# Boost_Gauge_MainBoard.net
KiCad netlist of a schematic drawn in EAGLE
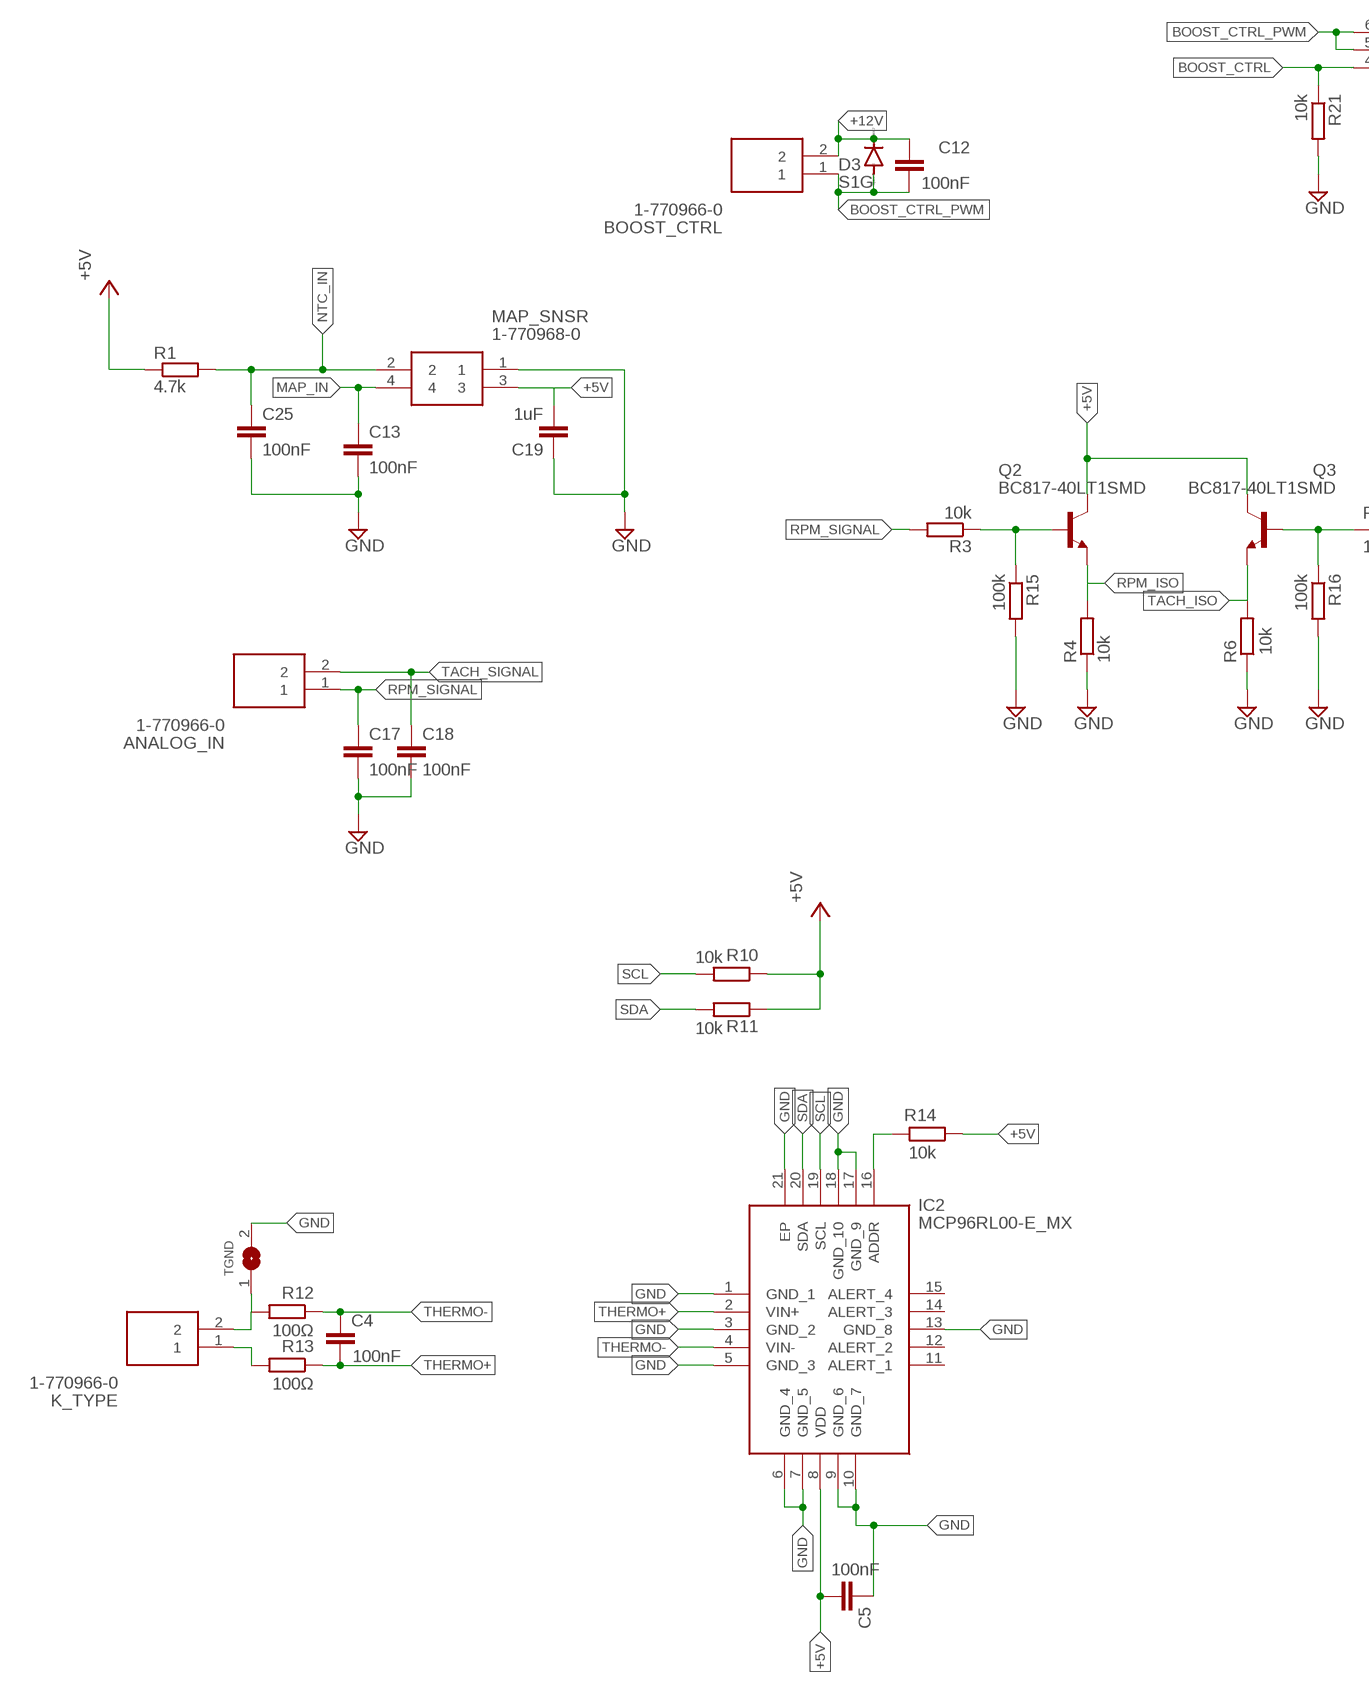
[diagram p0: schematic, sheet 1, part 1 of 2]
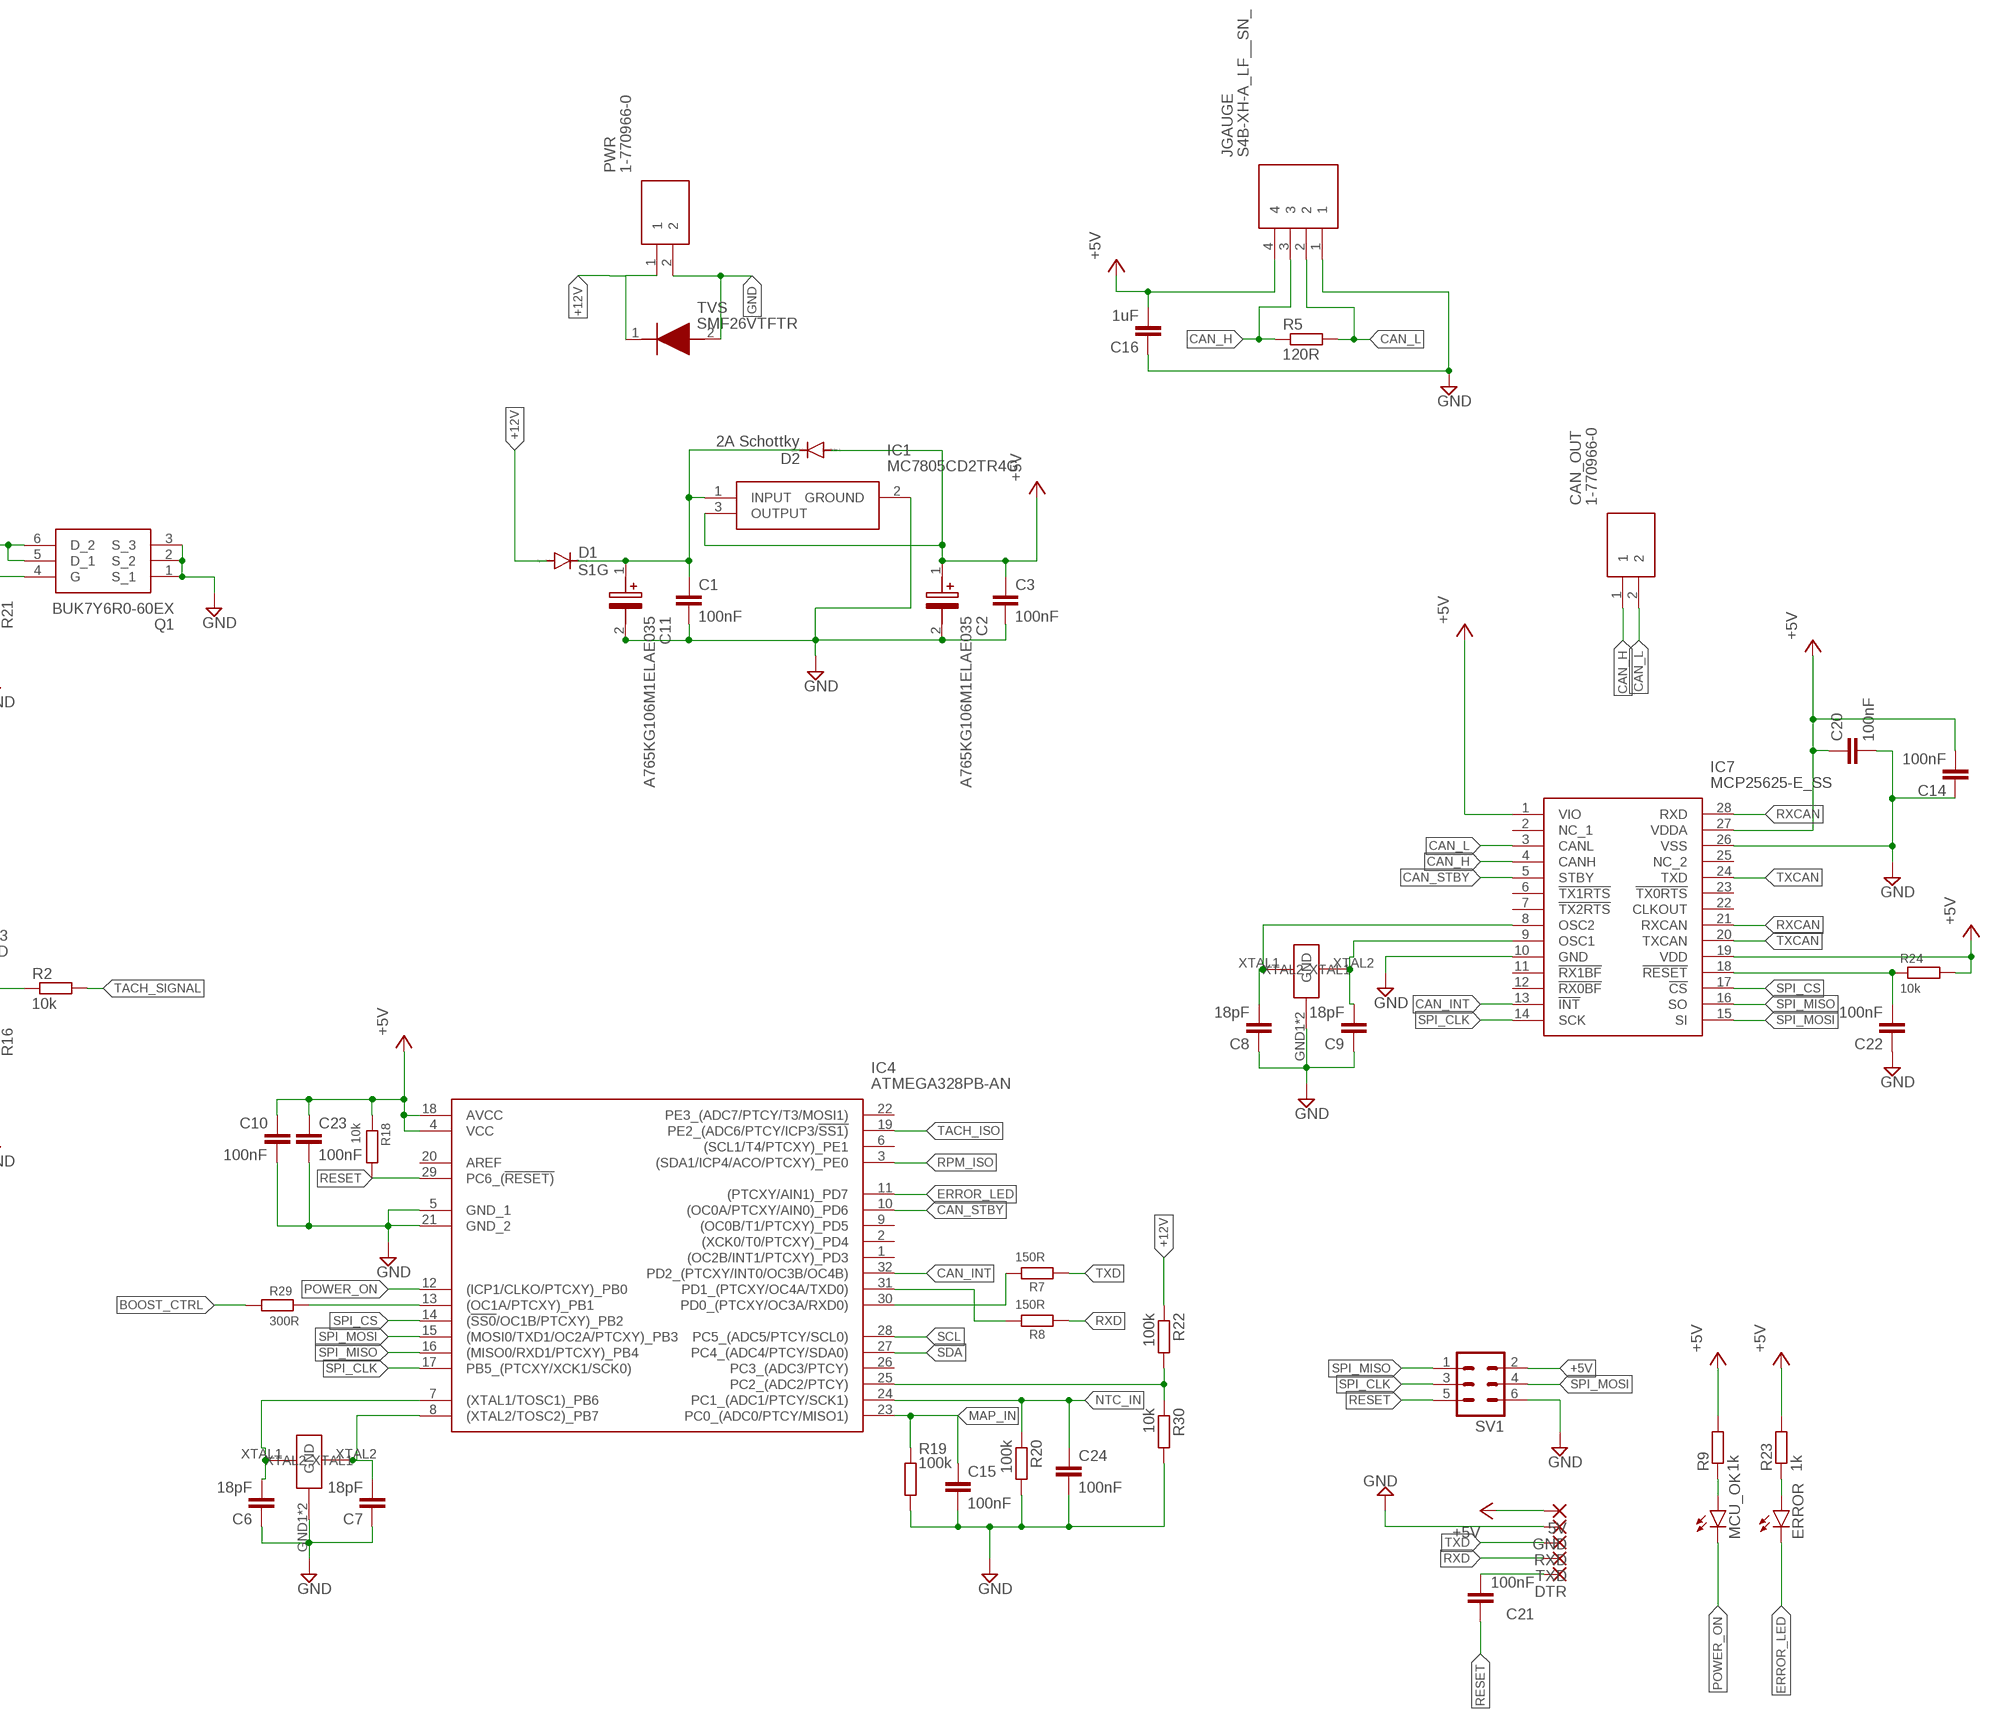
[diagram p1: schematic, sheet 1, part 2 of 2]

(export (version "E")
  (design (tool "Eeschema 10.0.6"))
  (components
    (comp (ref "5V")
      (value "1,6/0,9")
      (footprint "eagle-import:1,6_0,9")
      (libsource (lib "eagle-import") (part "1,6/0,9"))
    )
    (comp (ref "ANALOG_IN")
      (value "1-770966-0")
      (footprint "eagle-import:17709660")
      (fields (field (name "MOUSER_PART_NUMBER") "571-1-770966-0"))
      (libsource (lib "eagle-import") (part "1-770966-0"))
    )
    (comp (ref "BOOST_CTRL")
      (value "1-770966-0")
      (footprint "eagle-import:17709660")
      (fields (field (name "MOUSER_PART_NUMBER") "571-1-770966-0"))
      (libsource (lib "eagle-import") (part "1-770966-0"))
    )
    (comp (ref "C1")
      (value "100nF")
      (footprint "eagle-import:C0805")
      (libsource (lib "eagle-import") (part "C-EUC0805"))
    )
    (comp (ref "C2")
      (value "A765KG106M1ELAE035")
      (footprint "eagle-import:CAPAE830X730N")
      (fields (field (name "MOUSER_PART_NUMBER") "80-A765KG106M1ELAE35"))
      (libsource (lib "eagle-import") (part "A765KG106M1ELAE035"))
    )
    (comp (ref "C3")
      (value "100nF")
      (footprint "eagle-import:C0805")
      (libsource (lib "eagle-import") (part "C-EUC0805"))
    )
    (comp (ref "C4")
      (value "100nF")
      (footprint "eagle-import:C0805")
      (libsource (lib "eagle-import") (part "C-EUC0805"))
    )
    (comp (ref "C5")
      (value "100nF")
      (footprint "eagle-import:C0805")
      (libsource (lib "eagle-import") (part "C-EUC0805"))
    )
    (comp (ref "C6")
      (value "18pF")
      (footprint "eagle-import:C0805")
      (libsource (lib "eagle-import") (part "C-EUC0805"))
    )
    (comp (ref "C7")
      (value "18pF")
      (footprint "eagle-import:C0805")
      (libsource (lib "eagle-import") (part "C-EUC0805"))
    )
    (comp (ref "C8")
      (value "18pF")
      (footprint "eagle-import:C0805")
      (libsource (lib "eagle-import") (part "C-EUC0805"))
    )
    (comp (ref "C9")
      (value "18pF")
      (footprint "eagle-import:C0805")
      (libsource (lib "eagle-import") (part "C-EUC0805"))
    )
    (comp (ref "C10")
      (value "100nF")
      (footprint "eagle-import:C0805")
      (libsource (lib "eagle-import") (part "C-EUC0805"))
    )
    (comp (ref "C11")
      (value "A765KG106M1ELAE035")
      (footprint "eagle-import:CAPAE830X730N")
      (fields (field (name "MOUSER_PART_NUMBER") "80-A765KG106M1ELAE35"))
      (libsource (lib "eagle-import") (part "A765KG106M1ELAE035"))
    )
    (comp (ref "C12")
      (value "100nF")
      (footprint "eagle-import:C0805")
      (libsource (lib "eagle-import") (part "C-EUC0805"))
    )
    (comp (ref "C13")
      (value "100nF")
      (footprint "eagle-import:C0805")
      (libsource (lib "eagle-import") (part "C-EUC0805"))
    )
    (comp (ref "C14")
      (value "100nF")
      (footprint "eagle-import:C0805")
      (libsource (lib "eagle-import") (part "C-EUC0805"))
    )
    (comp (ref "C15")
      (value "100nF")
      (footprint "eagle-import:C0805")
      (libsource (lib "eagle-import") (part "C-EUC0805"))
    )
    (comp (ref "C16")
      (value "1uF")
      (footprint "eagle-import:C0805")
      (libsource (lib "eagle-import") (part "C-EUC0805"))
    )
    (comp (ref "C17")
      (value "100nF")
      (footprint "eagle-import:C0805")
      (libsource (lib "eagle-import") (part "C-EUC0805"))
    )
    (comp (ref "C18")
      (value "100nF")
      (footprint "eagle-import:C0805")
      (libsource (lib "eagle-import") (part "C-EUC0805"))
    )
    (comp (ref "C19")
      (value "1uF")
      (footprint "eagle-import:C0805")
      (libsource (lib "eagle-import") (part "C-EUC0805"))
    )
    (comp (ref "C20")
      (value "100nF")
      (footprint "eagle-import:C0805")
      (libsource (lib "eagle-import") (part "C-EUC0805"))
    )
    (comp (ref "C21")
      (value "100nF")
      (footprint "eagle-import:C0805")
      (libsource (lib "eagle-import") (part "C-EUC0805"))
    )
    (comp (ref "C22")
      (value "100nF")
      (footprint "eagle-import:C0805")
      (libsource (lib "eagle-import") (part "C-EUC0805"))
    )
    (comp (ref "C23")
      (value "100nF")
      (footprint "eagle-import:C0805")
      (libsource (lib "eagle-import") (part "C-EUC0805"))
    )
    (comp (ref "C24")
      (value "100nF")
      (footprint "eagle-import:C0805")
      (libsource (lib "eagle-import") (part "C-EUC0805"))
    )
    (comp (ref "C25")
      (value "100nF")
      (footprint "eagle-import:C0805")
      (libsource (lib "eagle-import") (part "C-EUC0805"))
    )
    (comp (ref "CAN_OUT")
      (value "1-770966-0")
      (footprint "eagle-import:17709660")
      (fields (field (name "MOUSER_PART_NUMBER") "571-1-770966-0"))
      (libsource (lib "eagle-import") (part "1-770966-0"))
    )
    (comp (ref "D1")
      (value "S1G")
      (footprint "eagle-import:DO-214AC")
      (libsource (lib "eagle-import") (part "DIODE-DO-214AC"))
    )
    (comp (ref "D2")
      (value "2A Schottky")
      (footprint "eagle-import:DO-214AC")
      (libsource (lib "eagle-import") (part "DIODE-DO-214AC"))
    )
    (comp (ref "D3")
      (value "S1G")
      (footprint "eagle-import:DO-214AC")
      (libsource (lib "eagle-import") (part "DIODE-DO-214AC"))
    )
    (comp (ref "DTR")
      (value "1,6/0,9")
      (footprint "eagle-import:1,6_0,9")
      (libsource (lib "eagle-import") (part "1,6/0,9"))
    )
    (comp (ref "ERROR")
      (value "LEDCHIPLED_1206")
      (footprint "eagle-import:CHIPLED_1206")
      (libsource (lib "eagle-import") (part "LEDCHIPLED_1206"))
    )
    (comp (ref "GND")
      (value "1,6/0,9")
      (footprint "eagle-import:1,6_0,9")
      (libsource (lib "eagle-import") (part "1,6/0,9"))
    )
    (comp (ref "IC1")
      (value "MC7805CD2TR4G")
      (footprint "eagle-import:MC7805CD2TR4G")
      (fields (field (name "MOUSER_PART_NUMBER") "863-MC7805CD2TR4G"))
      (libsource (lib "eagle-import") (part "MC7805CD2TR4G"))
    )
    (comp (ref "IC2")
      (value "MCP96RL00-E_MX")
      (footprint "eagle-import:QFN65P500X500X100-21N")
      (fields
        (field (name "MANUFACTURER_PART_NUMBER") "MCP96RL00-E/MX")
        (field (name "MOUSER_PART_NUMBER") "579-MCP96RL00-E/MX")
      )
      (libsource (lib "eagle-import") (part "MCP96RL00-E_MX"))
    )
    (comp (ref "IC4")
      (value "ATMEGA328PB-AN")
      (footprint "eagle-import:QFP80P900X900X120-32N")
      (fields (field (name "MOUSER_PART_NUMBER") "556-ATMEGA328PB-AN"))
      (libsource (lib "eagle-import") (part "ATMEGA328PB-AN"))
    )
    (comp (ref "IC7")
      (value "MCP25625-E_SS")
      (footprint "eagle-import:SOP65P780X200-28N")
      (fields
        (field (name "MANUFACTURER_PART_NUMBER") "MCP25625-E/SS")
        (field (name "MOUSER_PART_NUMBER") "579-MCP25625-E/SS")
      )
      (libsource (lib "eagle-import") (part "MCP25625-E_SS"))
    )
    (comp (ref "JGAUGE")
      (value "S4B-XH-A_LF__SN_")
      (footprint "eagle-import:S4BXHALFSN")
      (fields (field (name "MANUFACTURER_PART_NUMBER") "S4B-XH-A(LF)(SN)"))
      (libsource (lib "eagle-import") (part "S4B-XH-A_LF__SN_"))
    )
    (comp (ref "K_TYPE")
      (value "1-770966-0")
      (footprint "eagle-import:17709660")
      (fields (field (name "MOUSER_PART_NUMBER") "571-1-770966-0"))
      (libsource (lib "eagle-import") (part "1-770966-0"))
    )
    (comp (ref "MAP_SNSR")
      (value "1-770968-0")
      (footprint "eagle-import:17709680")
      (fields (field (name "MOUSER_PART_NUMBER") "571-1-770968-0"))
      (libsource (lib "eagle-import") (part "1-770968-0"))
    )
    (comp (ref "MCU_OK")
      (value "LEDCHIPLED_1206")
      (footprint "eagle-import:CHIPLED_1206")
      (libsource (lib "eagle-import") (part "LEDCHIPLED_1206"))
    )
    (comp (ref "PWR")
      (value "1-770966-0")
      (footprint "eagle-import:17709660")
      (fields (field (name "MOUSER_PART_NUMBER") "571-1-770966-0"))
      (libsource (lib "eagle-import") (part "1-770966-0"))
    )
    (comp (ref "Q1")
      (value "BUK7Y6R0-60EX")
      (footprint "eagle-import:BUK7Y6R060EX")
      (fields (field (name "MOUSER_PART_NUMBER") "771-BUK7Y6R0-60EX"))
      (libsource (lib "eagle-import") (part "BUK7Y6R0-60EX"))
    )
    (comp (ref "Q2")
      (value "BC817-40LT1SMD")
      (footprint "eagle-import:SOT23-BEC")
      (libsource (lib "eagle-import") (part "BC817SMD-40LT1"))
    )
    (comp (ref "Q3")
      (value "BC817-40LT1SMD")
      (footprint "eagle-import:SOT23-BEC")
      (libsource (lib "eagle-import") (part "BC817SMD-40LT1"))
    )
    (comp (ref "R1")
      (value "4.7k")
      (footprint "eagle-import:R0805")
      (libsource (lib "eagle-import") (part "R-EU_R0805"))
    )
    (comp (ref "R2")
      (value "10k")
      (footprint "eagle-import:R0805")
      (libsource (lib "eagle-import") (part "R-EU_R0805"))
    )
    (comp (ref "R3")
      (value "10k")
      (footprint "eagle-import:R0805")
      (libsource (lib "eagle-import") (part "R-EU_R0805"))
    )
    (comp (ref "R4")
      (value "10k")
      (footprint "eagle-import:R0805")
      (libsource (lib "eagle-import") (part "R-EU_R0805"))
    )
    (comp (ref "R5")
      (value "120R")
      (footprint "eagle-import:R1206")
      (libsource (lib "eagle-import") (part "R-EU_R1206"))
    )
    (comp (ref "R6")
      (value "10k")
      (footprint "eagle-import:R0805")
      (libsource (lib "eagle-import") (part "R-EU_R0805"))
    )
    (comp (ref "R7")
      (value "150R")
      (footprint "eagle-import:R0805")
      (libsource (lib "eagle-import") (part "R-EU_R0805"))
    )
    (comp (ref "R8")
      (value "150R")
      (footprint "eagle-import:R0805")
      (libsource (lib "eagle-import") (part "R-EU_R0805"))
    )
    (comp (ref "R9")
      (value "1k")
      (footprint "eagle-import:R0805")
      (libsource (lib "eagle-import") (part "R-EU_R0805"))
    )
    (comp (ref "R10")
      (value "10k")
      (footprint "eagle-import:R0805")
      (libsource (lib "eagle-import") (part "R-EU_R0805"))
    )
    (comp (ref "R11")
      (value "10k")
      (footprint "eagle-import:R0805")
      (libsource (lib "eagle-import") (part "R-EU_R0805"))
    )
    (comp (ref "R12")
      (value "100Ω")
      (footprint "eagle-import:R0805")
      (libsource (lib "eagle-import") (part "R-EU_R0805"))
    )
    (comp (ref "R13")
      (value "100Ω")
      (footprint "eagle-import:R0805")
      (libsource (lib "eagle-import") (part "R-EU_R0805"))
    )
    (comp (ref "R14")
      (value "10k")
      (footprint "eagle-import:R0805")
      (libsource (lib "eagle-import") (part "R-EU_R0805"))
    )
    (comp (ref "R15")
      (value "100k")
      (footprint "eagle-import:R0805")
      (libsource (lib "eagle-import") (part "R-EU_R0805"))
    )
    (comp (ref "R16")
      (value "100k")
      (footprint "eagle-import:R0805")
      (libsource (lib "eagle-import") (part "R-EU_R0805"))
    )
    (comp (ref "R18")
      (value "10k")
      (footprint "eagle-import:R0805")
      (libsource (lib "eagle-import") (part "R-EU_R0805"))
    )
    (comp (ref "R19")
      (value "100k")
      (footprint "eagle-import:R0805")
      (libsource (lib "eagle-import") (part "R-EU_R0805"))
    )
    (comp (ref "R20")
      (value "100k")
      (footprint "eagle-import:R0805")
      (libsource (lib "eagle-import") (part "R-EU_R0805"))
    )
    (comp (ref "R21")
      (value "10k")
      (footprint "eagle-import:R0805")
      (libsource (lib "eagle-import") (part "R-EU_R0805"))
    )
    (comp (ref "R22")
      (value "100k")
      (footprint "eagle-import:R0805")
      (libsource (lib "eagle-import") (part "R-EU_R0805"))
    )
    (comp (ref "R23")
      (value "1k")
      (footprint "eagle-import:R0805")
      (libsource (lib "eagle-import") (part "R-EU_R0805"))
    )
    (comp (ref "R24")
      (value "10k")
      (footprint "eagle-import:R0805")
      (libsource (lib "eagle-import") (part "R-EU_R0805"))
    )
    (comp (ref "R29")
      (value "300R")
      (footprint "eagle-import:R0805")
      (libsource (lib "eagle-import") (part "R-EU_R0805"))
    )
    (comp (ref "R30")
      (value "10k")
      (footprint "eagle-import:R0805")
      (libsource (lib "eagle-import") (part "R-EU_R0805"))
    )
    (comp (ref "RXD")
      (value "1,6/0,9")
      (footprint "eagle-import:1,6_0,9")
      (libsource (lib "eagle-import") (part "1,6/0,9"))
    )
    (comp (ref "SV1")
      (value "MA03-2")
      (footprint "eagle-import:MA03-2")
      (libsource (lib "eagle-import") (part "MA03-2"))
    )
    (comp (ref "TGND")
      (value "SOLDERJUMPER")
      (footprint "eagle-import:SOLDERJUMPER_ARROW_NOPASTE")
      (libsource (lib "eagle-import") (part "SOLDERJUMPER"))
    )
    (comp (ref "TVS")
      (value "SMF26VTFTR")
      (footprint "eagle-import:SMF26VTFTR")
      (fields (field (name "MOUSER_PART_NUMBER") "755-SMF26VTFTR"))
      (libsource (lib "eagle-import") (part "SMF26VTFTR"))
    )
    (comp (ref "TXD")
      (value "1,6/0,9")
      (footprint "eagle-import:1,6_0,9")
      (libsource (lib "eagle-import") (part "1,6/0,9"))
    )
    (comp (ref "U$4")
      (value "E3X160181X04")
      (footprint "eagle-import:E3X160181X04")
      (libsource (lib "eagle-import") (part "E3X160181X04"))
    )
    (comp (ref "U$5")
      (value "E3X160181X04")
      (footprint "eagle-import:E3X160181X04")
      (libsource (lib "eagle-import") (part "E3X160181X04"))
    )
  )
  (nets
    (net (code "1") (name "+5V") (class "Default")
      (node (ref "5V") (pin "1") (pinfunction "P_1") (pintype "passive"))
      (node (ref "C10") (pin "1") (pinfunction "1_1") (pintype "passive"))
      (node (ref "C14") (pin "2") (pinfunction "2_2") (pintype "passive"))
      (node (ref "C16") (pin "2") (pinfunction "2_2") (pintype "passive"))
      (node (ref "C19") (pin "2") (pinfunction "2_2") (pintype "passive"))
      (node (ref "C2") (pin "1") (pinfunction "+_1") (pintype "bidirectional"))
      (node (ref "C20") (pin "1") (pinfunction "1_1") (pintype "passive"))
      (node (ref "C23") (pin "1") (pinfunction "1_1") (pintype "passive"))
      (node (ref "C3") (pin "1") (pinfunction "1_1") (pintype "passive"))
      (node (ref "C5") (pin "2") (pinfunction "2_2") (pintype "passive"))
      (node (ref "D2") (pin "A") (pinfunction "A_A") (pintype "passive"))
      (node (ref "IC1") (pin "3") (pinfunction "OUTPUT_3") (pintype "bidirectional"))
      (node (ref "IC2") (pin "8") (pinfunction "VDD_8") (pintype "bidirectional"))
      (node (ref "IC4") (pin "18") (pinfunction "AVCC_18") (pintype "bidirectional"))
      (node (ref "IC4") (pin "4") (pinfunction "VCC_4") (pintype "bidirectional"))
      (node (ref "IC7") (pin "1") (pinfunction "VIO_1") (pintype "bidirectional"))
      (node (ref "IC7") (pin "19") (pinfunction "VDD_19") (pintype "bidirectional"))
      (node (ref "IC7") (pin "27") (pinfunction "VDDA_27") (pintype "bidirectional"))
      (node (ref "JGAUGE") (pin "4") (pinfunction "4_4") (pintype "bidirectional"))
      (node (ref "MAP_SNSR") (pin "3") (pinfunction "3_3") (pintype "bidirectional"))
      (node (ref "Q2") (pin "C") (pinfunction "C_C") (pintype "passive"))
      (node (ref "Q3") (pin "C") (pinfunction "C_C") (pintype "passive"))
      (node (ref "R1") (pin "1") (pinfunction "1_1") (pintype "passive"))
      (node (ref "R10") (pin "1") (pinfunction "1_1") (pintype "passive"))
      (node (ref "R11") (pin "1") (pinfunction "1_1") (pintype "passive"))
      (node (ref "R14") (pin "1") (pinfunction "1_1") (pintype "passive"))
      (node (ref "R18") (pin "1") (pinfunction "1_1") (pintype "passive"))
      (node (ref "R23") (pin "2") (pinfunction "2_2") (pintype "passive"))
      (node (ref "R24") (pin "2") (pinfunction "2_2") (pintype "passive"))
      (node (ref "R9") (pin "2") (pinfunction "2_2") (pintype "passive"))
      (node (ref "SV1") (pin "2") (pinfunction "2_2") (pintype "passive"))
    )
    (net (code "2") (name "+12V") (class "Default")
      (node (ref "BOOST_CTRL") (pin "2") (pinfunction "2_2") (pintype "bidirectional"))
      (node (ref "C12") (pin "2") (pinfunction "2_2") (pintype "passive"))
      (node (ref "D1") (pin "A") (pinfunction "A_A") (pintype "passive"))
      (node (ref "D3") (pin "C") (pinfunction "C_C") (pintype "passive"))
      (node (ref "PWR") (pin "1") (pinfunction "1_1") (pintype "bidirectional"))
      (node (ref "R22") (pin "1") (pinfunction "1_1") (pintype "passive"))
      (node (ref "TVS") (pin "1") (pinfunction "K_1") (pintype "bidirectional"))
    )
    (net (code "3") (name "BOOST_CTRL") (class "Default")
      (node (ref "Q1") (pin "4") (pinfunction "G_4") (pintype "bidirectional"))
      (node (ref "R21") (pin "1") (pinfunction "1_1") (pintype "passive"))
      (node (ref "R29") (pin "1") (pinfunction "1_1") (pintype "passive"))
    )
    (net (code "4") (name "BOOST_CTRL_PWM") (class "Default")
      (node (ref "BOOST_CTRL") (pin "1") (pinfunction "1_1") (pintype "bidirectional"))
      (node (ref "C12") (pin "1") (pinfunction "1_1") (pintype "passive"))
      (node (ref "D3") (pin "A") (pinfunction "A_A") (pintype "passive"))
      (node (ref "Q1") (pin "5") (pinfunction "D_1_5") (pintype "bidirectional"))
      (node (ref "Q1") (pin "6") (pinfunction "D_2_6") (pintype "bidirectional"))
    )
    (net (code "5") (name "CAN_H") (class "Default")
      (node (ref "CAN_OUT") (pin "1") (pinfunction "1_1") (pintype "bidirectional"))
      (node (ref "IC7") (pin "4") (pinfunction "CANH_4") (pintype "bidirectional"))
      (node (ref "JGAUGE") (pin "3") (pinfunction "3_3") (pintype "bidirectional"))
      (node (ref "R5") (pin "1") (pinfunction "1_1") (pintype "passive"))
    )
    (net (code "6") (name "CAN_INT") (class "Default")
      (node (ref "IC4") (pin "32") (pinfunction "PD2_(PTCXY/INT0/OC3B/OC4B)_32") (pintype "bidirectional"))
      (node (ref "IC7") (pin "13") (pinfunction "~{INT}_13") (pintype "bidirectional"))
    )
    (net (code "7") (name "CAN_L") (class "Default")
      (node (ref "CAN_OUT") (pin "2") (pinfunction "2_2") (pintype "bidirectional"))
      (node (ref "IC7") (pin "3") (pinfunction "CANL_3") (pintype "bidirectional"))
      (node (ref "JGAUGE") (pin "2") (pinfunction "2_2") (pintype "bidirectional"))
      (node (ref "R5") (pin "2") (pinfunction "2_2") (pintype "passive"))
    )
    (net (code "8") (name "CAN_STBY") (class "Default")
      (node (ref "IC4") (pin "10") (pinfunction "(OC0A/PTCXY/AIN0)_PD6_10") (pintype "bidirectional"))
      (node (ref "IC7") (pin "5") (pinfunction "STBY_5") (pintype "bidirectional"))
    )
    (net (code "9") (name "ERROR_LED") (class "Default")
      (node (ref "ERROR") (pin "C") (pinfunction "C_C") (pintype "passive"))
      (node (ref "IC4") (pin "11") (pinfunction "(PTCXY/AIN1)_PD7_11") (pintype "bidirectional"))
    )
    (net (code "10") (name "GND") (class "Default")
      (node (ref "C1") (pin "2") (pinfunction "2_2") (pintype "passive"))
      (node (ref "C10") (pin "2") (pinfunction "2_2") (pintype "passive"))
      (node (ref "C11") (pin "2") (pinfunction "-_2") (pintype "bidirectional"))
      (node (ref "C13") (pin "2") (pinfunction "2_2") (pintype "passive"))
      (node (ref "C14") (pin "1") (pinfunction "1_1") (pintype "passive"))
      (node (ref "C15") (pin "2") (pinfunction "2_2") (pintype "passive"))
      (node (ref "C16") (pin "1") (pinfunction "1_1") (pintype "passive"))
      (node (ref "C17") (pin "2") (pinfunction "2_2") (pintype "passive"))
      (node (ref "C18") (pin "2") (pinfunction "2_2") (pintype "passive"))
      (node (ref "C19") (pin "1") (pinfunction "1_1") (pintype "passive"))
      (node (ref "C2") (pin "2") (pinfunction "-_2") (pintype "bidirectional"))
      (node (ref "C20") (pin "2") (pinfunction "2_2") (pintype "passive"))
      (node (ref "C22") (pin "1") (pinfunction "1_1") (pintype "passive"))
      (node (ref "C23") (pin "2") (pinfunction "2_2") (pintype "passive"))
      (node (ref "C24") (pin "2") (pinfunction "2_2") (pintype "passive"))
      (node (ref "C25") (pin "2") (pinfunction "2_2") (pintype "passive"))
      (node (ref "C3") (pin "2") (pinfunction "2_2") (pintype "passive"))
      (node (ref "C5") (pin "1") (pinfunction "1_1") (pintype "passive"))
      (node (ref "C6") (pin "1") (pinfunction "1_1") (pintype "passive"))
      (node (ref "C7") (pin "1") (pinfunction "1_1") (pintype "passive"))
      (node (ref "C8") (pin "1") (pinfunction "1_1") (pintype "passive"))
      (node (ref "C9") (pin "1") (pinfunction "1_1") (pintype "passive"))
      (node (ref "GND") (pin "1") (pinfunction "P_1") (pintype "passive"))
      (node (ref "IC1") (pin "2") (pinfunction "GROUND_2") (pintype "bidirectional"))
      (node (ref "IC2") (pin "1") (pinfunction "GND_1_1") (pintype "bidirectional"))
      (node (ref "IC2") (pin "10") (pinfunction "GND_7_10") (pintype "bidirectional"))
      (node (ref "IC2") (pin "13") (pinfunction "GND_8_13") (pintype "bidirectional"))
      (node (ref "IC2") (pin "17") (pinfunction "GND_9_17") (pintype "bidirectional"))
      (node (ref "IC2") (pin "18") (pinfunction "GND_10_18") (pintype "bidirectional"))
      (node (ref "IC2") (pin "21") (pinfunction "EP_21") (pintype "bidirectional"))
      (node (ref "IC2") (pin "3") (pinfunction "GND_2_3") (pintype "bidirectional"))
      (node (ref "IC2") (pin "5") (pinfunction "GND_3_5") (pintype "bidirectional"))
      (node (ref "IC2") (pin "6") (pinfunction "GND_4_6") (pintype "bidirectional"))
      (node (ref "IC2") (pin "7") (pinfunction "GND_5_7") (pintype "bidirectional"))
      (node (ref "IC2") (pin "9") (pinfunction "GND_6_9") (pintype "bidirectional"))
      (node (ref "IC4") (pin "21") (pinfunction "GND_2_21") (pintype "bidirectional"))
      (node (ref "IC4") (pin "5") (pinfunction "GND_1_5") (pintype "bidirectional"))
      (node (ref "IC7") (pin "10") (pinfunction "GND_10") (pintype "bidirectional"))
      (node (ref "IC7") (pin "26") (pinfunction "VSS_26") (pintype "bidirectional"))
      (node (ref "JGAUGE") (pin "1") (pinfunction "1_1") (pintype "bidirectional"))
      (node (ref "MAP_SNSR") (pin "1") (pinfunction "1_1") (pintype "bidirectional"))
      (node (ref "PWR") (pin "2") (pinfunction "2_2") (pintype "bidirectional"))
      (node (ref "Q1") (pin "1") (pinfunction "S_1_1") (pintype "bidirectional"))
      (node (ref "Q1") (pin "2") (pinfunction "S_2_2") (pintype "bidirectional"))
      (node (ref "Q1") (pin "3") (pinfunction "S_3_3") (pintype "bidirectional"))
      (node (ref "R15") (pin "2") (pinfunction "2_2") (pintype "passive"))
      (node (ref "R16") (pin "2") (pinfunction "2_2") (pintype "passive"))
      (node (ref "R19") (pin "2") (pinfunction "2_2") (pintype "passive"))
      (node (ref "R20") (pin "2") (pinfunction "2_2") (pintype "passive"))
      (node (ref "R21") (pin "2") (pinfunction "2_2") (pintype "passive"))
      (node (ref "R30") (pin "2") (pinfunction "2_2") (pintype "passive"))
      (node (ref "R4") (pin "1") (pinfunction "1_1") (pintype "passive"))
      (node (ref "R6") (pin "1") (pinfunction "1_1") (pintype "passive"))
      (node (ref "SV1") (pin "6") (pinfunction "6_6") (pintype "passive"))
      (node (ref "TGND") (pin "2") (pinfunction "2_2") (pintype "passive"))
      (node (ref "TVS") (pin "2") (pinfunction "A_2") (pintype "bidirectional"))
      (node (ref "U$4") (pin "GND1") (pinfunction "GND_GND1") (pintype "bidirectional"))
      (node (ref "U$4") (pin "GND2") (pinfunction "GND_GND2") (pintype "bidirectional"))
      (node (ref "U$5") (pin "GND1") (pinfunction "GND_GND1") (pintype "bidirectional"))
      (node (ref "U$5") (pin "GND2") (pinfunction "GND_GND2") (pintype "bidirectional"))
    )
    (net (code "11") (name "MAP_IN") (class "Default")
      (node (ref "C13") (pin "1") (pinfunction "1_1") (pintype "passive"))
      (node (ref "C15") (pin "1") (pinfunction "1_1") (pintype "passive"))
      (node (ref "IC4") (pin "23") (pinfunction "PC0_(ADC0/PTCY/MISO1)_23") (pintype "bidirectional"))
      (node (ref "MAP_SNSR") (pin "4") (pinfunction "4_4") (pintype "bidirectional"))
      (node (ref "R19") (pin "1") (pinfunction "1_1") (pintype "passive"))
    )
    (net (code "12") (name "NTC_IN") (class "Default")
      (node (ref "C24") (pin "1") (pinfunction "1_1") (pintype "passive"))
      (node (ref "C25") (pin "1") (pinfunction "1_1") (pintype "passive"))
      (node (ref "IC4") (pin "24") (pinfunction "PC1_(ADC1/PTCY/SCK1)_24") (pintype "bidirectional"))
      (node (ref "MAP_SNSR") (pin "2") (pinfunction "2_2") (pintype "bidirectional"))
      (node (ref "R1") (pin "2") (pinfunction "2_2") (pintype "passive"))
      (node (ref "R20") (pin "1") (pinfunction "1_1") (pintype "passive"))
    )
    (net (code "13") (name "Net-(C11-+)") (class "Default")
      (node (ref "C1") (pin "1") (pinfunction "1_1") (pintype "passive"))
      (node (ref "C11") (pin "1") (pinfunction "+_1") (pintype "bidirectional"))
      (node (ref "D1") (pin "C") (pinfunction "C_C") (pintype "passive"))
      (node (ref "D2") (pin "C") (pinfunction "C_C") (pintype "passive"))
      (node (ref "IC1") (pin "1") (pinfunction "INPUT_1") (pintype "bidirectional"))
    )
    (net (code "14") (name "Net-(DTR-P)") (class "Default")
      (node (ref "C21") (pin "2") (pinfunction "2_2") (pintype "passive"))
      (node (ref "DTR") (pin "1") (pinfunction "P_1") (pintype "passive"))
    )
    (net (code "15") (name "Net-(ERROR-PadA)") (class "Default")
      (node (ref "ERROR") (pin "A") (pinfunction "A_A") (pintype "passive"))
      (node (ref "R23") (pin "1") (pinfunction "1_1") (pintype "passive"))
    )
    (net (code "16") (name "Net-(IC2-ADDR)") (class "Default")
      (node (ref "IC2") (pin "16") (pinfunction "ADDR_16") (pintype "bidirectional"))
      (node (ref "R14") (pin "2") (pinfunction "2_2") (pintype "passive"))
    )
    (net (code "17") (name "Net-(IC4-(OC1A{slash}PTCXY)_PB1)") (class "Default")
      (node (ref "IC4") (pin "13") (pinfunction "(OC1A/PTCXY)_PB1_13") (pintype "bidirectional"))
      (node (ref "R29") (pin "2") (pinfunction "2_2") (pintype "passive"))
    )
    (net (code "18") (name "Net-(IC4-(XTAL1{slash}TOSC1)_PB6)") (class "Default")
      (node (ref "C6") (pin "2") (pinfunction "2_2") (pintype "passive"))
      (node (ref "IC4") (pin "7") (pinfunction "(XTAL1/TOSC1)_PB6_7") (pintype "bidirectional"))
      (node (ref "U$4") (pin "XTAL1") (pinfunction "XTAL1_XTAL1") (pintype "bidirectional"))
    )
    (net (code "19") (name "Net-(IC4-(XTAL2{slash}TOSC2)_PB7)") (class "Default")
      (node (ref "C7") (pin "2") (pinfunction "2_2") (pintype "passive"))
      (node (ref "IC4") (pin "8") (pinfunction "(XTAL2/TOSC2)_PB7_8") (pintype "bidirectional"))
      (node (ref "U$4") (pin "XTAL2") (pinfunction "XTAL2_XTAL2") (pintype "bidirectional"))
    )
    (net (code "20") (name "Net-(IC4-PC2_(ADC2{slash}PTCY))") (class "Default")
      (node (ref "IC4") (pin "25") (pinfunction "PC2_(ADC2/PTCY)_25") (pintype "bidirectional"))
      (node (ref "R22") (pin "2") (pinfunction "2_2") (pintype "passive"))
      (node (ref "R30") (pin "1") (pinfunction "1_1") (pintype "passive"))
    )
    (net (code "21") (name "Net-(IC4-PD0_(PTCXY{slash}OC3A{slash}RXD0))") (class "Default")
      (node (ref "IC4") (pin "30") (pinfunction "PD0_(PTCXY/OC3A/RXD0)_30") (pintype "bidirectional"))
      (node (ref "R7") (pin "2") (pinfunction "2_2") (pintype "passive"))
    )
    (net (code "22") (name "Net-(IC4-PD1_(PTCXY{slash}OC4A{slash}TXD0))") (class "Default")
      (node (ref "IC4") (pin "31") (pinfunction "PD1_(PTCXY/OC4A/TXD0)_31") (pintype "bidirectional"))
      (node (ref "R8") (pin "2") (pinfunction "2_2") (pintype "passive"))
    )
    (net (code "23") (name "Net-(IC7-OSC1)") (class "Default")
      (node (ref "C9") (pin "2") (pinfunction "2_2") (pintype "passive"))
      (node (ref "IC7") (pin "9") (pinfunction "OSC1_9") (pintype "bidirectional"))
      (node (ref "U$5") (pin "XTAL2") (pinfunction "XTAL2_XTAL2") (pintype "bidirectional"))
    )
    (net (code "24") (name "Net-(IC7-OSC2)") (class "Default")
      (node (ref "C8") (pin "2") (pinfunction "2_2") (pintype "passive"))
      (node (ref "IC7") (pin "8") (pinfunction "OSC2_8") (pintype "bidirectional"))
      (node (ref "U$5") (pin "XTAL1") (pinfunction "XTAL1_XTAL1") (pintype "bidirectional"))
    )
    (net (code "25") (name "Net-(IC7-~{RESET})") (class "Default")
      (node (ref "C22") (pin "2") (pinfunction "2_2") (pintype "passive"))
      (node (ref "IC7") (pin "18") (pinfunction "~{RESET}_18") (pintype "bidirectional"))
      (node (ref "R24") (pin "1") (pinfunction "1_1") (pintype "passive"))
    )
    (net (code "26") (name "Net-(K_TYPE-Pad1)") (class "Default")
      (node (ref "K_TYPE") (pin "1") (pinfunction "1_1") (pintype "bidirectional"))
      (node (ref "R13") (pin "2") (pinfunction "2_2") (pintype "passive"))
    )
    (net (code "27") (name "Net-(K_TYPE-Pad2)") (class "Default")
      (node (ref "K_TYPE") (pin "2") (pinfunction "2_2") (pintype "bidirectional"))
      (node (ref "R12") (pin "2") (pinfunction "2_2") (pintype "passive"))
      (node (ref "TGND") (pin "1") (pinfunction "1_1") (pintype "passive"))
    )
    (net (code "28") (name "Net-(MCU_OK-PadA)") (class "Default")
      (node (ref "MCU_OK") (pin "A") (pinfunction "A_A") (pintype "passive"))
      (node (ref "R9") (pin "1") (pinfunction "1_1") (pintype "passive"))
    )
    (net (code "29") (name "Net-(Q2-PadB)") (class "Default")
      (node (ref "Q2") (pin "B") (pinfunction "B_B") (pintype "passive"))
      (node (ref "R15") (pin "1") (pinfunction "1_1") (pintype "passive"))
      (node (ref "R3") (pin "1") (pinfunction "1_1") (pintype "passive"))
    )
    (net (code "30") (name "Net-(Q3-PadB)") (class "Default")
      (node (ref "Q3") (pin "B") (pinfunction "B_B") (pintype "passive"))
      (node (ref "R16") (pin "1") (pinfunction "1_1") (pintype "passive"))
      (node (ref "R2") (pin "1") (pinfunction "1_1") (pintype "passive"))
    )
    (net (code "31") (name "POWER_ON") (class "Default")
      (node (ref "IC4") (pin "12") (pinfunction "(ICP1/CLKO/PTCXY)_PB0_12") (pintype "bidirectional"))
      (node (ref "MCU_OK") (pin "C") (pinfunction "C_C") (pintype "passive"))
    )
    (net (code "32") (name "RESET") (class "Default")
      (node (ref "C21") (pin "1") (pinfunction "1_1") (pintype "passive"))
      (node (ref "IC4") (pin "29") (pinfunction "PC6_(~{RESET})_29") (pintype "bidirectional"))
      (node (ref "R18") (pin "2") (pinfunction "2_2") (pintype "passive"))
      (node (ref "SV1") (pin "5") (pinfunction "5_5") (pintype "passive"))
    )
    (net (code "33") (name "RPM_ISO") (class "Default")
      (node (ref "IC4") (pin "3") (pinfunction "(SDA1/ICP4/ACO/PTCXY)_PE0_3") (pintype "bidirectional"))
      (node (ref "Q2") (pin "E") (pinfunction "E_E") (pintype "passive"))
      (node (ref "R4") (pin "2") (pinfunction "2_2") (pintype "passive"))
    )
    (net (code "34") (name "RPM_SIGNAL") (class "Default")
      (node (ref "ANALOG_IN") (pin "1") (pinfunction "1_1") (pintype "bidirectional"))
      (node (ref "C17") (pin "1") (pinfunction "1_1") (pintype "passive"))
      (node (ref "R3") (pin "2") (pinfunction "2_2") (pintype "passive"))
    )
    (net (code "35") (name "RXCAN") (class "Default")
      (node (ref "IC7") (pin "21") (pinfunction "RXCAN_21") (pintype "bidirectional"))
      (node (ref "IC7") (pin "28") (pinfunction "RXD_28") (pintype "bidirectional"))
    )
    (net (code "36") (name "RXD") (class "Default")
      (node (ref "R8") (pin "1") (pinfunction "1_1") (pintype "passive"))
      (node (ref "TXD") (pin "1") (pinfunction "P_1") (pintype "passive"))
    )
    (net (code "37") (name "SCL") (class "Default")
      (node (ref "IC2") (pin "19") (pinfunction "SCL_19") (pintype "bidirectional"))
      (node (ref "IC4") (pin "28") (pinfunction "PC5_(ADC5/PTCY/SCL0)_28") (pintype "bidirectional"))
      (node (ref "R10") (pin "2") (pinfunction "2_2") (pintype "passive"))
    )
    (net (code "38") (name "SDA") (class "Default")
      (node (ref "IC2") (pin "20") (pinfunction "SDA_20") (pintype "bidirectional"))
      (node (ref "IC4") (pin "27") (pinfunction "PC4_(ADC4/PTCY/SDA0)_27") (pintype "bidirectional"))
      (node (ref "R11") (pin "2") (pinfunction "2_2") (pintype "passive"))
    )
    (net (code "39") (name "SPI_CLK") (class "Default")
      (node (ref "IC4") (pin "17") (pinfunction "PB5_(PTCXY/XCK1/SCK0)_17") (pintype "bidirectional"))
      (node (ref "IC7") (pin "14") (pinfunction "SCK_14") (pintype "bidirectional"))
      (node (ref "SV1") (pin "3") (pinfunction "3_3") (pintype "passive"))
    )
    (net (code "40") (name "SPI_CS") (class "Default")
      (node (ref "IC4") (pin "14") (pinfunction "(~{SS0}/OC1B/PTCXY)_PB2_14") (pintype "bidirectional"))
      (node (ref "IC7") (pin "17") (pinfunction "~{CS}_17") (pintype "bidirectional"))
    )
    (net (code "41") (name "SPI_MISO") (class "Default")
      (node (ref "IC4") (pin "16") (pinfunction "(MISO0/RXD1/PTCXY)_PB4_16") (pintype "bidirectional"))
      (node (ref "IC7") (pin "16") (pinfunction "SO_16") (pintype "bidirectional"))
      (node (ref "SV1") (pin "1") (pinfunction "1_1") (pintype "passive"))
    )
    (net (code "42") (name "SPI_MOSI") (class "Default")
      (node (ref "IC4") (pin "15") (pinfunction "(MOSI0/TXD1/OC2A/PTCXY)_PB3_15") (pintype "bidirectional"))
      (node (ref "IC7") (pin "15") (pinfunction "SI_15") (pintype "bidirectional"))
      (node (ref "SV1") (pin "4") (pinfunction "4_4") (pintype "passive"))
    )
    (net (code "43") (name "TACH_ISO") (class "Default")
      (node (ref "IC4") (pin "19") (pinfunction "PE2_(ADC6/PTCY/ICP3/~{SS1})_19") (pintype "bidirectional"))
      (node (ref "Q3") (pin "E") (pinfunction "E_E") (pintype "passive"))
      (node (ref "R6") (pin "2") (pinfunction "2_2") (pintype "passive"))
    )
    (net (code "44") (name "TACH_SIGNAL") (class "Default")
      (node (ref "ANALOG_IN") (pin "2") (pinfunction "2_2") (pintype "bidirectional"))
      (node (ref "C18") (pin "1") (pinfunction "1_1") (pintype "passive"))
      (node (ref "R2") (pin "2") (pinfunction "2_2") (pintype "passive"))
    )
    (net (code "45") (name "THERMO+") (class "Default")
      (node (ref "C4") (pin "2") (pinfunction "2_2") (pintype "passive"))
      (node (ref "IC2") (pin "2") (pinfunction "VIN+_2") (pintype "bidirectional"))
      (node (ref "R13") (pin "1") (pinfunction "1_1") (pintype "passive"))
    )
    (net (code "46") (name "THERMO-") (class "Default")
      (node (ref "C4") (pin "1") (pinfunction "1_1") (pintype "passive"))
      (node (ref "IC2") (pin "4") (pinfunction "VIN-_4") (pintype "bidirectional"))
      (node (ref "R12") (pin "1") (pinfunction "1_1") (pintype "passive"))
    )
    (net (code "47") (name "TXCAN") (class "Default")
      (node (ref "IC7") (pin "20") (pinfunction "TXCAN_20") (pintype "bidirectional"))
      (node (ref "IC7") (pin "24") (pinfunction "TXD_24") (pintype "bidirectional"))
    )
    (net (code "48") (name "TXD") (class "Default")
      (node (ref "R7") (pin "1") (pinfunction "1_1") (pintype "passive"))
      (node (ref "RXD") (pin "1") (pinfunction "P_1") (pintype "passive"))
    )
    (net (code "49") (name "unconnected-(IC2-ALERT_1-Pad11)") (class "Default")
      (node (ref "IC2") (pin "11") (pinfunction "ALERT_1_11") (pintype "bidirectional"))
    )
    (net (code "50") (name "unconnected-(IC2-ALERT_2-Pad12)") (class "Default")
      (node (ref "IC2") (pin "12") (pinfunction "ALERT_2_12") (pintype "bidirectional"))
    )
    (net (code "51") (name "unconnected-(IC2-ALERT_3-Pad14)") (class "Default")
      (node (ref "IC2") (pin "14") (pinfunction "ALERT_3_14") (pintype "bidirectional"))
    )
    (net (code "52") (name "unconnected-(IC2-ALERT_4-Pad15)") (class "Default")
      (node (ref "IC2") (pin "15") (pinfunction "ALERT_4_15") (pintype "bidirectional"))
    )
    (net (code "53") (name "unconnected-(IC4-(OC0B{slash}T1{slash}PTCXY)_PD5-Pad9)") (class "Default")
      (node (ref "IC4") (pin "9") (pinfunction "(OC0B/T1/PTCXY)_PD5_9") (pintype "bidirectional"))
    )
    (net (code "54") (name "unconnected-(IC4-(OC2B{slash}INT1{slash}PTCXY)_PD3-Pad1)") (class "Default")
      (node (ref "IC4") (pin "1") (pinfunction "(OC2B/INT1/PTCXY)_PD3_1") (pintype "bidirectional"))
    )
    (net (code "55") (name "unconnected-(IC4-(SCL1{slash}T4{slash}PTCXY)_PE1-Pad6)") (class "Default")
      (node (ref "IC4") (pin "6") (pinfunction "(SCL1/T4/PTCXY)_PE1_6") (pintype "bidirectional"))
    )
    (net (code "56") (name "unconnected-(IC4-(XCK0{slash}T0{slash}PTCXY)_PD4-Pad2)") (class "Default")
      (node (ref "IC4") (pin "2") (pinfunction "(XCK0/T0/PTCXY)_PD4_2") (pintype "bidirectional"))
    )
    (net (code "57") (name "unconnected-(IC4-AREF-Pad20)") (class "Default")
      (node (ref "IC4") (pin "20") (pinfunction "AREF_20") (pintype "bidirectional"))
    )
    (net (code "58") (name "unconnected-(IC4-PC3_(ADC3{slash}PTCY)-Pad26)") (class "Default")
      (node (ref "IC4") (pin "26") (pinfunction "PC3_(ADC3/PTCY)_26") (pintype "bidirectional"))
    )
    (net (code "59") (name "unconnected-(IC4-PE3_(ADC7{slash}PTCY{slash}T3{slash}MOSI1)-Pad22)") (class "Default")
      (node (ref "IC4") (pin "22") (pinfunction "PE3_(ADC7/PTCY/T3/MOSI1)_22") (pintype "bidirectional"))
    )
    (net (code "60") (name "unconnected-(IC7-CLKOUT-Pad22)") (class "Default")
      (node (ref "IC7") (pin "22") (pinfunction "CLKOUT_22") (pintype "bidirectional"))
    )
    (net (code "61") (name "unconnected-(IC7-NC_1-Pad2)") (class "Default")
      (node (ref "IC7") (pin "2") (pinfunction "NC_1_2") (pintype "bidirectional"))
    )
    (net (code "62") (name "unconnected-(IC7-NC_2-Pad25)") (class "Default")
      (node (ref "IC7") (pin "25") (pinfunction "NC_2_25") (pintype "bidirectional"))
    )
    (net (code "63") (name "unconnected-(IC7-~{RX0BF}-Pad12)") (class "Default")
      (node (ref "IC7") (pin "12") (pinfunction "~{RX0BF}_12") (pintype "bidirectional"))
    )
    (net (code "64") (name "unconnected-(IC7-~{RX1BF}-Pad11)") (class "Default")
      (node (ref "IC7") (pin "11") (pinfunction "~{RX1BF}_11") (pintype "bidirectional"))
    )
    (net (code "65") (name "unconnected-(IC7-~{TX0RTS}-Pad23)") (class "Default")
      (node (ref "IC7") (pin "23") (pinfunction "~{TX0RTS}_23") (pintype "bidirectional"))
    )
    (net (code "66") (name "unconnected-(IC7-~{TX1RTS}-Pad6)") (class "Default")
      (node (ref "IC7") (pin "6") (pinfunction "~{TX1RTS}_6") (pintype "bidirectional"))
    )
    (net (code "67") (name "unconnected-(IC7-~{TX2RTS}-Pad7)") (class "Default")
      (node (ref "IC7") (pin "7") (pinfunction "~{TX2RTS}_7") (pintype "bidirectional"))
    )
  )
)
